# IMU.net
KiCad netlist of a schematic drawn in Altium Designer
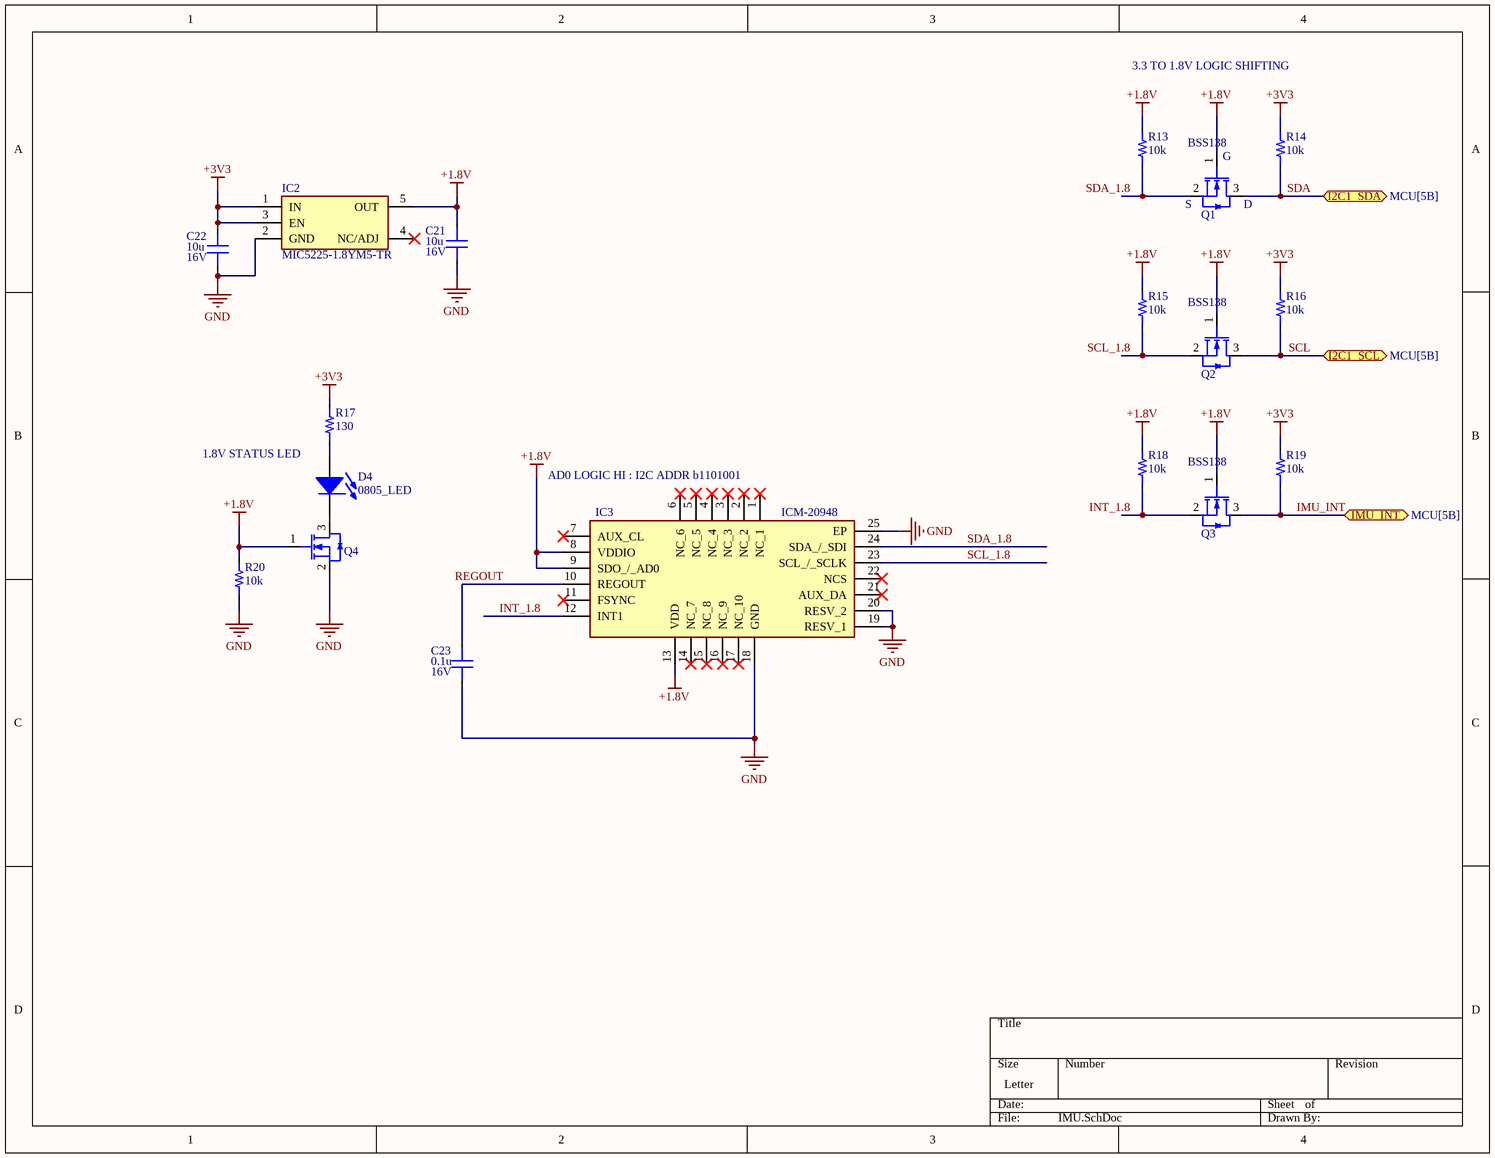
[diagram p0: IMU.SchDoc]

(export (version "E")
  (design (tool "Eeschema 10.0.6"))
  (components
    (comp (ref "C21")
      (value "10u")
      (footprint "0603_CAP")
      (fields (field (name "VOLTAGE") "16V") (field (name "Comment") "Capacitor"))
      (libsource (lib "Capacitors") (part "Capacitor"))
    )
    (comp (ref "C22")
      (value "10u")
      (footprint "0603_CAP")
      (fields (field (name "VOLTAGE") "16V") (field (name "Comment") "Capacitor"))
      (libsource (lib "Capacitors") (part "Capacitor"))
    )
    (comp (ref "C23")
      (value "0.1u")
      (footprint "0603_CAP")
      (fields (field (name "VOLTAGE") "16V") (field (name "Comment") "Capacitor"))
      (libsource (lib "Capacitors") (part "Capacitor"))
    )
    (comp (ref "D4")
      (value "0805_LED")
      (footprint "0805_LED")
      (description "Generic 0805 LED")
      (libsource (lib "Diodes") (part "0805_LED"))
    )
    (comp (ref "IC2")
      (value "MIC5225-1.8YM5-TR")
      (footprint "507_Part_Footprints:SOT95P280X130-5N")
      (description "Integrated Circuit")
      (fields (field (name "MOUSER PART NUMBER") "998-MIC5225-1.8YM5TR"))
      (libsource (lib "507_Parts") (part "MIC5225-1.8YM5-TR"))
    )
    (comp (ref "IC3")
      (value "ICM-20948")
      (footprint "QFN40P300X300X105-25N-D")
      (description "Integrated Circuit")
      (fields (field (name "MOUSER PART NUMBER") "410-ICM-20948"))
      (libsource (lib "507_Parts") (part "ICM-20948"))
    )
    (comp (ref "Q1")
      (value "BSS138")
      (footprint "SOT95P240X120-3N")
      (description "MOSFET (N-Channel)")
      (fields (field (name "MOUSER PART NUMBER") "512-BSS138"))
      (libsource (lib "507_Parts") (part "BSS138"))
    )
    (comp (ref "Q2")
      (value "BSS138")
      (footprint "SOT95P240X120-3N")
      (description "MOSFET (N-Channel)")
      (fields (field (name "MOUSER PART NUMBER") "512-BSS138"))
      (libsource (lib "507_Parts") (part "BSS138"))
    )
    (comp (ref "Q3")
      (value "BSS138")
      (footprint "SOT95P240X120-3N")
      (description "MOSFET (N-Channel)")
      (fields (field (name "MOUSER PART NUMBER") "512-BSS138"))
      (libsource (lib "507_Parts") (part "BSS138"))
    )
    (comp (ref "Q4")
      (value "BSS138")
      (footprint "SOT95P240X120-3N")
      (description "MOSFET (N-Channel)")
      (fields (field (name "MOUSER PART NUMBER") "512-BSS138"))
      (libsource (lib "507_Parts") (part "BSS138"))
    )
    (comp (ref "R13")
      (value "10k")
      (footprint "0603_RES")
      (fields (field (name "Comment") "Resistor"))
      (libsource (lib "Resistors") (part "Resistor"))
    )
    (comp (ref "R14")
      (value "10k")
      (footprint "0603_RES")
      (fields (field (name "Comment") "Resistor"))
      (libsource (lib "Resistors") (part "Resistor"))
    )
    (comp (ref "R15")
      (value "10k")
      (footprint "0603_RES")
      (fields (field (name "Comment") "Resistor"))
      (libsource (lib "Resistors") (part "Resistor"))
    )
    (comp (ref "R16")
      (value "10k")
      (footprint "0603_RES")
      (fields (field (name "Comment") "Resistor"))
      (libsource (lib "Resistors") (part "Resistor"))
    )
    (comp (ref "R17")
      (value "130")
      (footprint "0603_RES")
      (fields (field (name "Comment") "Resistor"))
      (libsource (lib "Resistors") (part "Resistor"))
    )
    (comp (ref "R18")
      (value "10k")
      (footprint "0603_RES")
      (fields (field (name "Comment") "Resistor"))
      (libsource (lib "Resistors") (part "Resistor"))
    )
    (comp (ref "R19")
      (value "10k")
      (footprint "0603_RES")
      (fields (field (name "Comment") "Resistor"))
      (libsource (lib "Resistors") (part "Resistor"))
    )
    (comp (ref "R20")
      (value "10k")
      (footprint "0603_RES")
      (fields (field (name "Comment") "Resistor"))
      (libsource (lib "Resistors") (part "Resistor"))
    )
  )
  (nets
    (net (code "1") (name "+1.8V") (class "Default")
      (node (ref "C21") (pin "2") (pinfunction "2_2") (pintype "passive"))
      (node (ref "IC2") (pin "5") (pinfunction "OUT_5") (pintype "passive"))
      (node (ref "IC3") (pin "13") (pinfunction "VDD_13") (pintype "passive"))
      (node (ref "IC3") (pin "8") (pinfunction "VDDIO_8") (pintype "passive"))
      (node (ref "IC3") (pin "9") (pinfunction "SDO_/_AD0_9") (pintype "passive"))
      (node (ref "Q1") (pin "1") (pinfunction "G_1") (pintype "passive"))
      (node (ref "Q2") (pin "1") (pinfunction "G_1") (pintype "passive"))
      (node (ref "Q3") (pin "1") (pinfunction "G_1") (pintype "passive"))
      (node (ref "Q4") (pin "1") (pinfunction "G_1") (pintype "passive"))
      (node (ref "R13") (pin "2") (pinfunction "2_2") (pintype "passive"))
      (node (ref "R15") (pin "2") (pinfunction "2_2") (pintype "passive"))
      (node (ref "R18") (pin "2") (pinfunction "2_2") (pintype "passive"))
      (node (ref "R20") (pin "2") (pinfunction "2_2") (pintype "passive"))
    )
    (net (code "2") (name "+3V3") (class "Default")
      (node (ref "C22") (pin "2") (pinfunction "2_2") (pintype "passive"))
      (node (ref "IC2") (pin "1") (pinfunction "IN_1") (pintype "passive"))
      (node (ref "IC2") (pin "3") (pinfunction "EN_3") (pintype "passive"))
      (node (ref "R14") (pin "2") (pinfunction "2_2") (pintype "passive"))
      (node (ref "R16") (pin "2") (pinfunction "2_2") (pintype "passive"))
      (node (ref "R17") (pin "2") (pinfunction "2_2") (pintype "passive"))
      (node (ref "R19") (pin "2") (pinfunction "2_2") (pintype "passive"))
    )
    (net (code "3") (name "/IMU_INT") (class "Default")
      (node (ref "Q3") (pin "3") (pinfunction "D_3") (pintype "passive"))
      (node (ref "R19") (pin "1") (pinfunction "1_1") (pintype "passive"))
    )
    (net (code "4") (name "/INT_1.8") (class "Default")
      (node (ref "IC3") (pin "12") (pinfunction "INT1_12") (pintype "passive"))
      (node (ref "Q3") (pin "2") (pinfunction "S_2") (pintype "passive"))
      (node (ref "R18") (pin "1") (pinfunction "1_1") (pintype "passive"))
    )
    (net (code "5") (name "/REGOUT") (class "Default")
      (node (ref "C23") (pin "2") (pinfunction "2_2") (pintype "passive"))
      (node (ref "IC3") (pin "10") (pinfunction "REGOUT_10") (pintype "passive"))
    )
    (net (code "6") (name "/SCL") (class "Default")
      (node (ref "Q2") (pin "3") (pinfunction "D_3") (pintype "passive"))
      (node (ref "R16") (pin "1") (pinfunction "1_1") (pintype "passive"))
    )
    (net (code "7") (name "/SCL_1.8") (class "Default")
      (node (ref "IC3") (pin "23") (pinfunction "SCL_/_SCLK_23") (pintype "passive"))
      (node (ref "Q2") (pin "2") (pinfunction "S_2") (pintype "passive"))
      (node (ref "R15") (pin "1") (pinfunction "1_1") (pintype "passive"))
    )
    (net (code "8") (name "/SDA") (class "Default")
      (node (ref "Q1") (pin "3") (pinfunction "D_3") (pintype "passive"))
      (node (ref "R14") (pin "1") (pinfunction "1_1") (pintype "passive"))
    )
    (net (code "9") (name "/SDA_1.8") (class "Default")
      (node (ref "IC3") (pin "24") (pinfunction "SDA_/_SDI_24") (pintype "passive"))
      (node (ref "Q1") (pin "2") (pinfunction "S_2") (pintype "passive"))
      (node (ref "R13") (pin "1") (pinfunction "1_1") (pintype "passive"))
    )
    (net (code "10") (name "GND") (class "Default")
      (node (ref "C21") (pin "1") (pinfunction "1_1") (pintype "passive"))
      (node (ref "C22") (pin "1") (pinfunction "1_1") (pintype "passive"))
      (node (ref "C23") (pin "1") (pinfunction "1_1") (pintype "passive"))
      (node (ref "IC2") (pin "2") (pinfunction "GND_2") (pintype "passive"))
      (node (ref "IC3") (pin "18") (pinfunction "GND_18") (pintype "passive"))
      (node (ref "IC3") (pin "19") (pinfunction "RESV_1_19") (pintype "passive"))
      (node (ref "IC3") (pin "20") (pinfunction "RESV_2_20") (pintype "passive"))
      (node (ref "IC3") (pin "25") (pinfunction "EP_25") (pintype "passive"))
      (node (ref "Q4") (pin "2") (pinfunction "S_2") (pintype "passive"))
      (node (ref "R20") (pin "1") (pinfunction "1_1") (pintype "passive"))
    )
    (net (code "11") (name "Net-(D4-A)") (class "Default")
      (node (ref "D4") (pin "1") (pinfunction "A_1") (pintype "passive"))
      (node (ref "R17") (pin "1") (pinfunction "1_1") (pintype "passive"))
    )
    (net (code "12") (name "Net-(D4-K)") (class "Default")
      (node (ref "D4") (pin "2") (pinfunction "K_2") (pintype "passive"))
      (node (ref "Q4") (pin "3") (pinfunction "D_3") (pintype "passive"))
    )
    (net (code "13") (name "unconnected-(IC2-NC{slash}ADJ-Pad4)") (class "Default")
      (node (ref "IC2") (pin "4") (pinfunction "NC/ADJ_4") (pintype "passive+no_connect"))
    )
    (net (code "14") (name "unconnected-(IC3-AUX_CL-Pad7)") (class "Default")
      (node (ref "IC3") (pin "7") (pinfunction "AUX_CL_7") (pintype "passive+no_connect"))
    )
    (net (code "15") (name "unconnected-(IC3-AUX_DA-Pad21)") (class "Default")
      (node (ref "IC3") (pin "21") (pinfunction "AUX_DA_21") (pintype "passive+no_connect"))
    )
    (net (code "16") (name "unconnected-(IC3-FSYNC-Pad11)") (class "Default")
      (node (ref "IC3") (pin "11") (pinfunction "FSYNC_11") (pintype "passive+no_connect"))
    )
    (net (code "17") (name "unconnected-(IC3-NCS-Pad22)") (class "Default")
      (node (ref "IC3") (pin "22") (pinfunction "NCS_22") (pintype "passive+no_connect"))
    )
    (net (code "18") (name "unconnected-(IC3-NC_1-Pad1)") (class "Default")
      (node (ref "IC3") (pin "1") (pinfunction "NC_1_1") (pintype "passive+no_connect"))
    )
    (net (code "19") (name "unconnected-(IC3-NC_2-Pad2)") (class "Default")
      (node (ref "IC3") (pin "2") (pinfunction "NC_2_2") (pintype "passive+no_connect"))
    )
    (net (code "20") (name "unconnected-(IC3-NC_3-Pad3)") (class "Default")
      (node (ref "IC3") (pin "3") (pinfunction "NC_3_3") (pintype "passive+no_connect"))
    )
    (net (code "21") (name "unconnected-(IC3-NC_4-Pad4)") (class "Default")
      (node (ref "IC3") (pin "4") (pinfunction "NC_4_4") (pintype "passive+no_connect"))
    )
    (net (code "22") (name "unconnected-(IC3-NC_5-Pad5)") (class "Default")
      (node (ref "IC3") (pin "5") (pinfunction "NC_5_5") (pintype "passive+no_connect"))
    )
    (net (code "23") (name "unconnected-(IC3-NC_6-Pad6)") (class "Default")
      (node (ref "IC3") (pin "6") (pinfunction "NC_6_6") (pintype "passive+no_connect"))
    )
    (net (code "24") (name "unconnected-(IC3-NC_7-Pad14)") (class "Default")
      (node (ref "IC3") (pin "14") (pinfunction "NC_7_14") (pintype "passive+no_connect"))
    )
    (net (code "25") (name "unconnected-(IC3-NC_8-Pad15)") (class "Default")
      (node (ref "IC3") (pin "15") (pinfunction "NC_8_15") (pintype "passive+no_connect"))
    )
    (net (code "26") (name "unconnected-(IC3-NC_9-Pad16)") (class "Default")
      (node (ref "IC3") (pin "16") (pinfunction "NC_9_16") (pintype "passive+no_connect"))
    )
    (net (code "27") (name "unconnected-(IC3-NC_10-Pad17)") (class "Default")
      (node (ref "IC3") (pin "17") (pinfunction "NC_10_17") (pintype "passive+no_connect"))
    )
  )
)
